# pcb.net
KiCad netlist of a schematic drawn in EAGLE
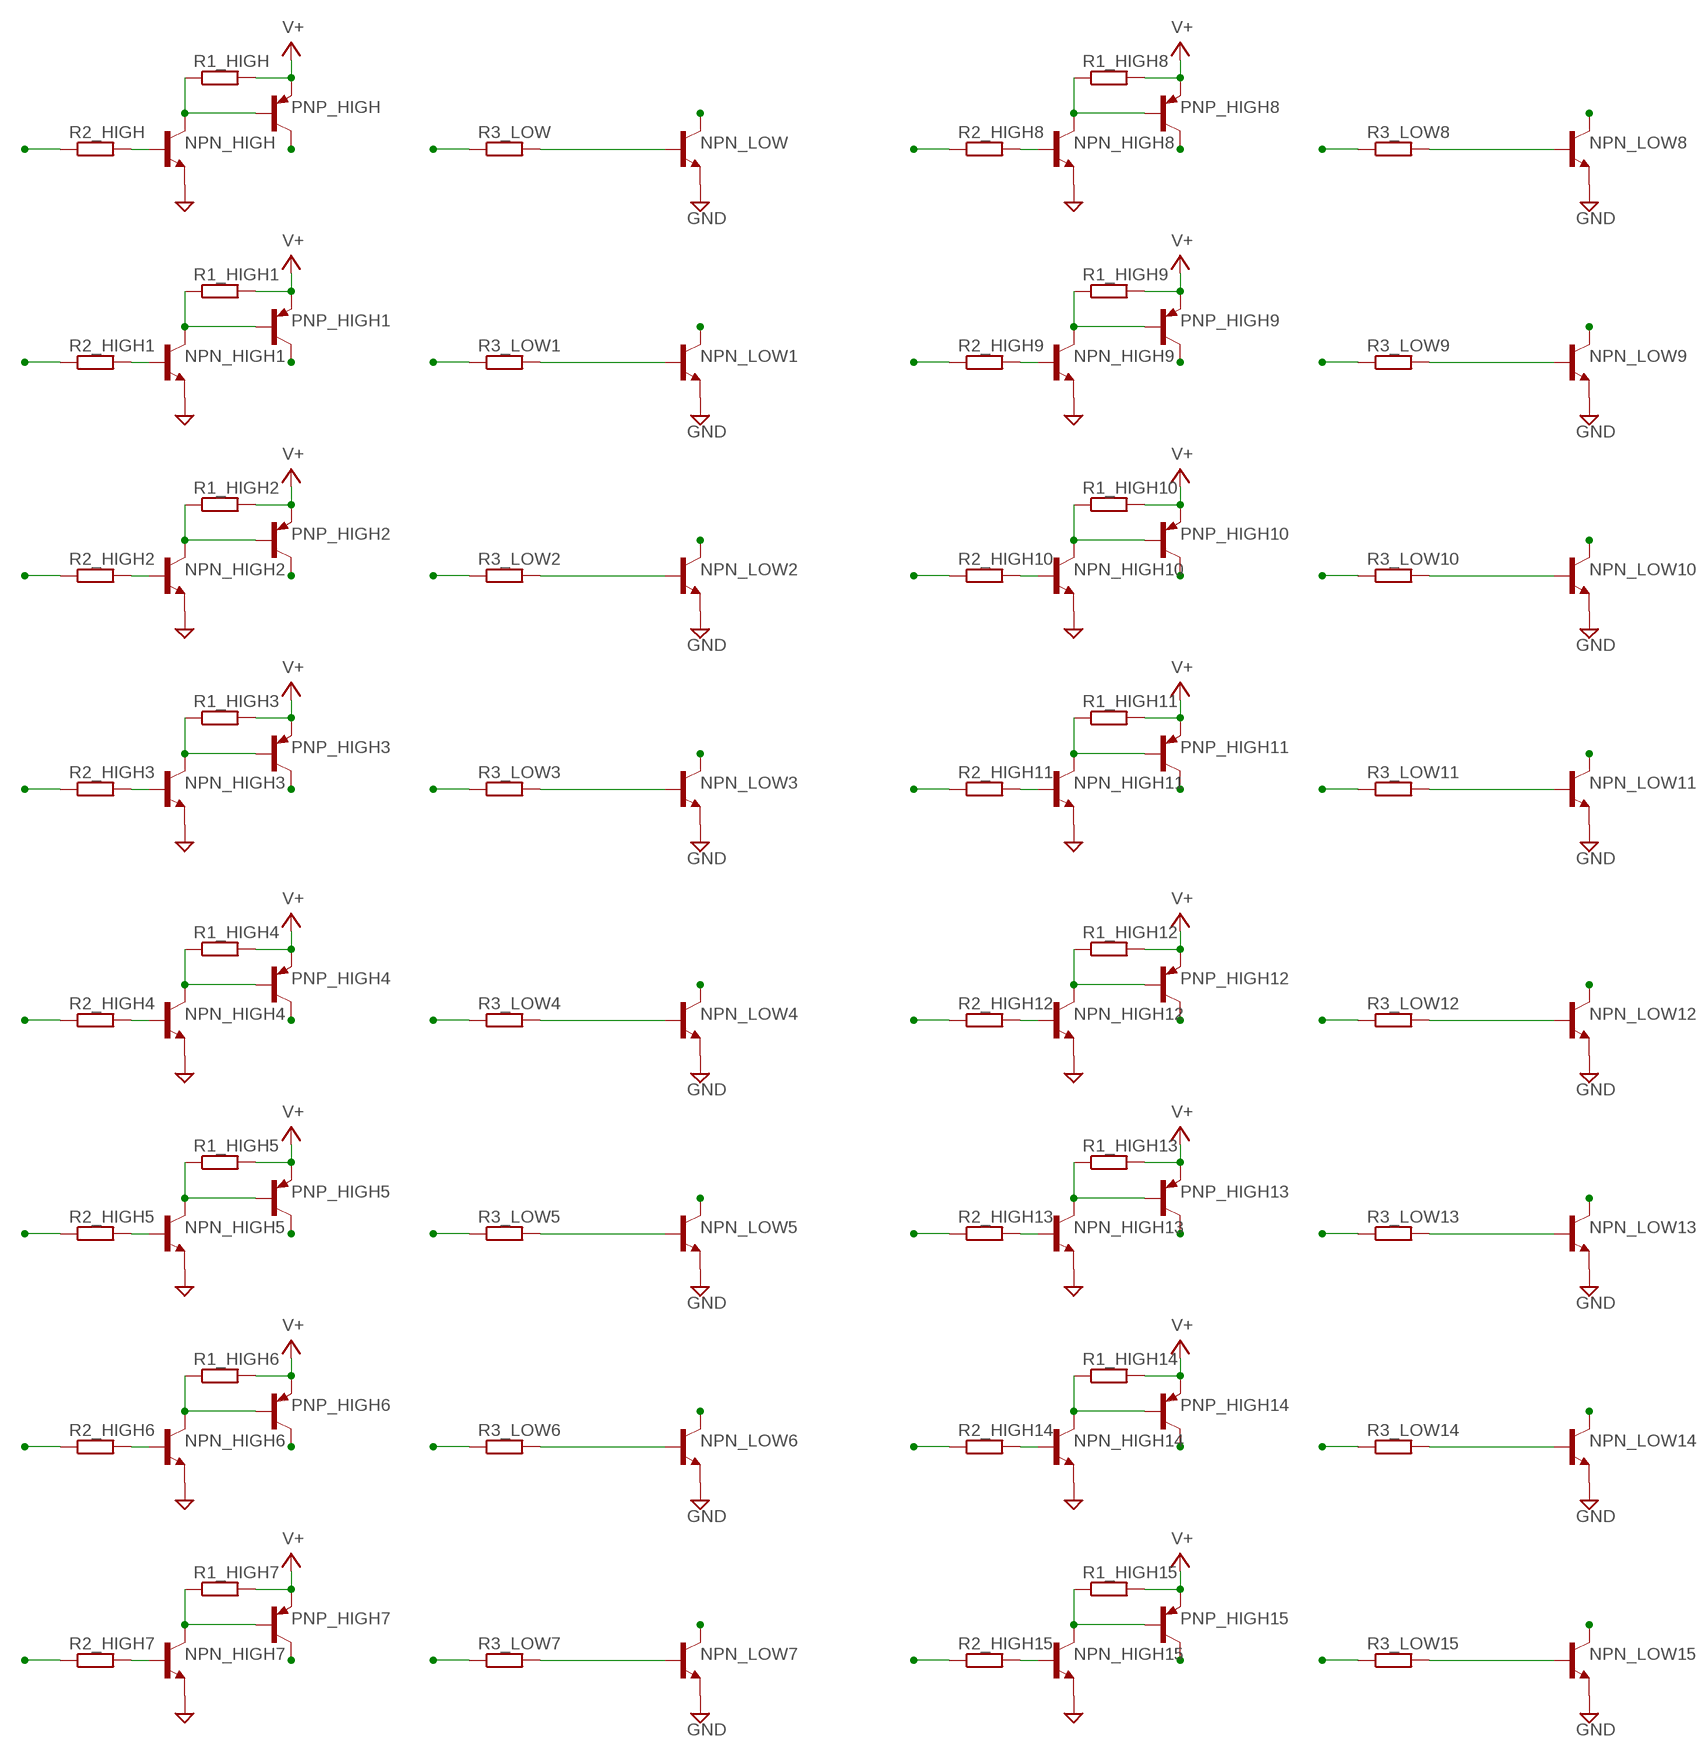
[diagram p0: schematic, sheet 1]

(export (version "E")
  (design (tool "Eeschema 10.0.6"))
  (components
    (comp (ref "NPN_HIGH")
      (value "-NPN-TO92-ECB")
      (footprint "eagle-import:TO92-ECB")
      (libsource (lib "eagle-import") (part "-NPN-TO92-ECB"))
    )
    (comp (ref "NPN_HIGH1")
      (value "-NPN-TO92-ECB")
      (footprint "eagle-import:TO92-ECB")
      (libsource (lib "eagle-import") (part "-NPN-TO92-ECB"))
    )
    (comp (ref "NPN_HIGH2")
      (value "-NPN-TO92-ECB")
      (footprint "eagle-import:TO92-ECB")
      (libsource (lib "eagle-import") (part "-NPN-TO92-ECB"))
    )
    (comp (ref "NPN_HIGH3")
      (value "-NPN-TO92-ECB")
      (footprint "eagle-import:TO92-ECB")
      (libsource (lib "eagle-import") (part "-NPN-TO92-ECB"))
    )
    (comp (ref "NPN_HIGH4")
      (value "-NPN-TO92-ECB")
      (footprint "eagle-import:TO92-ECB")
      (libsource (lib "eagle-import") (part "-NPN-TO92-ECB"))
    )
    (comp (ref "NPN_HIGH5")
      (value "-NPN-TO92-ECB")
      (footprint "eagle-import:TO92-ECB")
      (libsource (lib "eagle-import") (part "-NPN-TO92-ECB"))
    )
    (comp (ref "NPN_HIGH6")
      (value "-NPN-TO92-ECB")
      (footprint "eagle-import:TO92-ECB")
      (libsource (lib "eagle-import") (part "-NPN-TO92-ECB"))
    )
    (comp (ref "NPN_HIGH7")
      (value "-NPN-TO92-ECB")
      (footprint "eagle-import:TO92-ECB")
      (libsource (lib "eagle-import") (part "-NPN-TO92-ECB"))
    )
    (comp (ref "NPN_HIGH8")
      (value "-NPN-TO92-ECB")
      (footprint "eagle-import:TO92-ECB")
      (libsource (lib "eagle-import") (part "-NPN-TO92-ECB"))
    )
    (comp (ref "NPN_HIGH9")
      (value "-NPN-TO92-ECB")
      (footprint "eagle-import:TO92-ECB")
      (libsource (lib "eagle-import") (part "-NPN-TO92-ECB"))
    )
    (comp (ref "NPN_HIGH10")
      (value "-NPN-TO92-ECB")
      (footprint "eagle-import:TO92-ECB")
      (libsource (lib "eagle-import") (part "-NPN-TO92-ECB"))
    )
    (comp (ref "NPN_HIGH11")
      (value "-NPN-TO92-ECB")
      (footprint "eagle-import:TO92-ECB")
      (libsource (lib "eagle-import") (part "-NPN-TO92-ECB"))
    )
    (comp (ref "NPN_HIGH12")
      (value "-NPN-TO92-ECB")
      (footprint "eagle-import:TO92-ECB")
      (libsource (lib "eagle-import") (part "-NPN-TO92-ECB"))
    )
    (comp (ref "NPN_HIGH13")
      (value "-NPN-TO92-ECB")
      (footprint "eagle-import:TO92-ECB")
      (libsource (lib "eagle-import") (part "-NPN-TO92-ECB"))
    )
    (comp (ref "NPN_HIGH14")
      (value "-NPN-TO92-ECB")
      (footprint "eagle-import:TO92-ECB")
      (libsource (lib "eagle-import") (part "-NPN-TO92-ECB"))
    )
    (comp (ref "NPN_HIGH15")
      (value "-NPN-TO92-ECB")
      (footprint "eagle-import:TO92-ECB")
      (libsource (lib "eagle-import") (part "-NPN-TO92-ECB"))
    )
    (comp (ref "NPN_LOW")
      (value "-NPN-TO92-ECB")
      (footprint "eagle-import:TO92-ECB")
      (libsource (lib "eagle-import") (part "-NPN-TO92-ECB"))
    )
    (comp (ref "NPN_LOW1")
      (value "-NPN-TO92-ECB")
      (footprint "eagle-import:TO92-ECB")
      (libsource (lib "eagle-import") (part "-NPN-TO92-ECB"))
    )
    (comp (ref "NPN_LOW2")
      (value "-NPN-TO92-ECB")
      (footprint "eagle-import:TO92-ECB")
      (libsource (lib "eagle-import") (part "-NPN-TO92-ECB"))
    )
    (comp (ref "NPN_LOW3")
      (value "-NPN-TO92-ECB")
      (footprint "eagle-import:TO92-ECB")
      (libsource (lib "eagle-import") (part "-NPN-TO92-ECB"))
    )
    (comp (ref "NPN_LOW4")
      (value "-NPN-TO92-ECB")
      (footprint "eagle-import:TO92-ECB")
      (libsource (lib "eagle-import") (part "-NPN-TO92-ECB"))
    )
    (comp (ref "NPN_LOW5")
      (value "-NPN-TO92-ECB")
      (footprint "eagle-import:TO92-ECB")
      (libsource (lib "eagle-import") (part "-NPN-TO92-ECB"))
    )
    (comp (ref "NPN_LOW6")
      (value "-NPN-TO92-ECB")
      (footprint "eagle-import:TO92-ECB")
      (libsource (lib "eagle-import") (part "-NPN-TO92-ECB"))
    )
    (comp (ref "NPN_LOW7")
      (value "-NPN-TO92-ECB")
      (footprint "eagle-import:TO92-ECB")
      (libsource (lib "eagle-import") (part "-NPN-TO92-ECB"))
    )
    (comp (ref "NPN_LOW8")
      (value "-NPN-TO92-ECB")
      (footprint "eagle-import:TO92-ECB")
      (libsource (lib "eagle-import") (part "-NPN-TO92-ECB"))
    )
    (comp (ref "NPN_LOW9")
      (value "-NPN-TO92-ECB")
      (footprint "eagle-import:TO92-ECB")
      (libsource (lib "eagle-import") (part "-NPN-TO92-ECB"))
    )
    (comp (ref "NPN_LOW10")
      (value "-NPN-TO92-ECB")
      (footprint "eagle-import:TO92-ECB")
      (libsource (lib "eagle-import") (part "-NPN-TO92-ECB"))
    )
    (comp (ref "NPN_LOW11")
      (value "-NPN-TO92-ECB")
      (footprint "eagle-import:TO92-ECB")
      (libsource (lib "eagle-import") (part "-NPN-TO92-ECB"))
    )
    (comp (ref "NPN_LOW12")
      (value "-NPN-TO92-ECB")
      (footprint "eagle-import:TO92-ECB")
      (libsource (lib "eagle-import") (part "-NPN-TO92-ECB"))
    )
    (comp (ref "NPN_LOW13")
      (value "-NPN-TO92-ECB")
      (footprint "eagle-import:TO92-ECB")
      (libsource (lib "eagle-import") (part "-NPN-TO92-ECB"))
    )
    (comp (ref "NPN_LOW14")
      (value "-NPN-TO92-ECB")
      (footprint "eagle-import:TO92-ECB")
      (libsource (lib "eagle-import") (part "-NPN-TO92-ECB"))
    )
    (comp (ref "NPN_LOW15")
      (value "-NPN-TO92-ECB")
      (footprint "eagle-import:TO92-ECB")
      (libsource (lib "eagle-import") (part "-NPN-TO92-ECB"))
    )
    (comp (ref "PNP_HIGH")
      (value "-PNP-TO92-BEC")
      (footprint "eagle-import:TO92-BEC")
      (libsource (lib "eagle-import") (part "-PNP-TO92-BEC"))
    )
    (comp (ref "PNP_HIGH1")
      (value "-PNP-TO92-BEC")
      (footprint "eagle-import:TO92-BEC")
      (libsource (lib "eagle-import") (part "-PNP-TO92-BEC"))
    )
    (comp (ref "PNP_HIGH2")
      (value "-PNP-TO92-BEC")
      (footprint "eagle-import:TO92-BEC")
      (libsource (lib "eagle-import") (part "-PNP-TO92-BEC"))
    )
    (comp (ref "PNP_HIGH3")
      (value "-PNP-TO92-BEC")
      (footprint "eagle-import:TO92-BEC")
      (libsource (lib "eagle-import") (part "-PNP-TO92-BEC"))
    )
    (comp (ref "PNP_HIGH4")
      (value "-PNP-TO92-BEC")
      (footprint "eagle-import:TO92-BEC")
      (libsource (lib "eagle-import") (part "-PNP-TO92-BEC"))
    )
    (comp (ref "PNP_HIGH5")
      (value "-PNP-TO92-BEC")
      (footprint "eagle-import:TO92-BEC")
      (libsource (lib "eagle-import") (part "-PNP-TO92-BEC"))
    )
    (comp (ref "PNP_HIGH6")
      (value "-PNP-TO92-BEC")
      (footprint "eagle-import:TO92-BEC")
      (libsource (lib "eagle-import") (part "-PNP-TO92-BEC"))
    )
    (comp (ref "PNP_HIGH7")
      (value "-PNP-TO92-BEC")
      (footprint "eagle-import:TO92-BEC")
      (libsource (lib "eagle-import") (part "-PNP-TO92-BEC"))
    )
    (comp (ref "PNP_HIGH8")
      (value "-PNP-TO92-BEC")
      (footprint "eagle-import:TO92-BEC")
      (libsource (lib "eagle-import") (part "-PNP-TO92-BEC"))
    )
    (comp (ref "PNP_HIGH9")
      (value "-PNP-TO92-BEC")
      (footprint "eagle-import:TO92-BEC")
      (libsource (lib "eagle-import") (part "-PNP-TO92-BEC"))
    )
    (comp (ref "PNP_HIGH10")
      (value "-PNP-TO92-BEC")
      (footprint "eagle-import:TO92-BEC")
      (libsource (lib "eagle-import") (part "-PNP-TO92-BEC"))
    )
    (comp (ref "PNP_HIGH11")
      (value "-PNP-TO92-BEC")
      (footprint "eagle-import:TO92-BEC")
      (libsource (lib "eagle-import") (part "-PNP-TO92-BEC"))
    )
    (comp (ref "PNP_HIGH12")
      (value "-PNP-TO92-BEC")
      (footprint "eagle-import:TO92-BEC")
      (libsource (lib "eagle-import") (part "-PNP-TO92-BEC"))
    )
    (comp (ref "PNP_HIGH13")
      (value "-PNP-TO92-BEC")
      (footprint "eagle-import:TO92-BEC")
      (libsource (lib "eagle-import") (part "-PNP-TO92-BEC"))
    )
    (comp (ref "PNP_HIGH14")
      (value "-PNP-TO92-BEC")
      (footprint "eagle-import:TO92-BEC")
      (libsource (lib "eagle-import") (part "-PNP-TO92-BEC"))
    )
    (comp (ref "PNP_HIGH15")
      (value "-PNP-TO92-BEC")
      (footprint "eagle-import:TO92-BEC")
      (libsource (lib "eagle-import") (part "-PNP-TO92-BEC"))
    )
    (comp (ref "R1_HIGH")
      (value "R-EU_0613/15")
      (footprint "eagle-import:P0613_15")
      (libsource (lib "eagle-import") (part "R-EU_0613/15"))
    )
    (comp (ref "R1_HIGH1")
      (value "R-EU_0613/15")
      (footprint "eagle-import:P0613_15")
      (libsource (lib "eagle-import") (part "R-EU_0613/15"))
    )
    (comp (ref "R1_HIGH2")
      (value "R-EU_0613/15")
      (footprint "eagle-import:P0613_15")
      (libsource (lib "eagle-import") (part "R-EU_0613/15"))
    )
    (comp (ref "R1_HIGH3")
      (value "R-EU_0613/15")
      (footprint "eagle-import:P0613_15")
      (libsource (lib "eagle-import") (part "R-EU_0613/15"))
    )
    (comp (ref "R1_HIGH4")
      (value "R-EU_0613/15")
      (footprint "eagle-import:P0613_15")
      (libsource (lib "eagle-import") (part "R-EU_0613/15"))
    )
    (comp (ref "R1_HIGH5")
      (value "R-EU_0613/15")
      (footprint "eagle-import:P0613_15")
      (libsource (lib "eagle-import") (part "R-EU_0613/15"))
    )
    (comp (ref "R1_HIGH6")
      (value "R-EU_0613/15")
      (footprint "eagle-import:P0613_15")
      (libsource (lib "eagle-import") (part "R-EU_0613/15"))
    )
    (comp (ref "R1_HIGH7")
      (value "R-EU_0613/15")
      (footprint "eagle-import:P0613_15")
      (libsource (lib "eagle-import") (part "R-EU_0613/15"))
    )
    (comp (ref "R1_HIGH8")
      (value "R-EU_0613/15")
      (footprint "eagle-import:P0613_15")
      (libsource (lib "eagle-import") (part "R-EU_0613/15"))
    )
    (comp (ref "R1_HIGH9")
      (value "R-EU_0613/15")
      (footprint "eagle-import:P0613_15")
      (libsource (lib "eagle-import") (part "R-EU_0613/15"))
    )
    (comp (ref "R1_HIGH10")
      (value "R-EU_0613/15")
      (footprint "eagle-import:P0613_15")
      (libsource (lib "eagle-import") (part "R-EU_0613/15"))
    )
    (comp (ref "R1_HIGH11")
      (value "R-EU_0613/15")
      (footprint "eagle-import:P0613_15")
      (libsource (lib "eagle-import") (part "R-EU_0613/15"))
    )
    (comp (ref "R1_HIGH12")
      (value "R-EU_0613/15")
      (footprint "eagle-import:P0613_15")
      (libsource (lib "eagle-import") (part "R-EU_0613/15"))
    )
    (comp (ref "R1_HIGH13")
      (value "R-EU_0613/15")
      (footprint "eagle-import:P0613_15")
      (libsource (lib "eagle-import") (part "R-EU_0613/15"))
    )
    (comp (ref "R1_HIGH14")
      (value "R-EU_0613/15")
      (footprint "eagle-import:P0613_15")
      (libsource (lib "eagle-import") (part "R-EU_0613/15"))
    )
    (comp (ref "R1_HIGH15")
      (value "R-EU_0613/15")
      (footprint "eagle-import:P0613_15")
      (libsource (lib "eagle-import") (part "R-EU_0613/15"))
    )
    (comp (ref "R2_HIGH")
      (value "R-EU_0613/15")
      (footprint "eagle-import:P0613_15")
      (libsource (lib "eagle-import") (part "R-EU_0613/15"))
    )
    (comp (ref "R2_HIGH1")
      (value "R-EU_0613/15")
      (footprint "eagle-import:P0613_15")
      (libsource (lib "eagle-import") (part "R-EU_0613/15"))
    )
    (comp (ref "R2_HIGH2")
      (value "R-EU_0613/15")
      (footprint "eagle-import:P0613_15")
      (libsource (lib "eagle-import") (part "R-EU_0613/15"))
    )
    (comp (ref "R2_HIGH3")
      (value "R-EU_0613/15")
      (footprint "eagle-import:P0613_15")
      (libsource (lib "eagle-import") (part "R-EU_0613/15"))
    )
    (comp (ref "R2_HIGH4")
      (value "R-EU_0613/15")
      (footprint "eagle-import:P0613_15")
      (libsource (lib "eagle-import") (part "R-EU_0613/15"))
    )
    (comp (ref "R2_HIGH5")
      (value "R-EU_0613/15")
      (footprint "eagle-import:P0613_15")
      (libsource (lib "eagle-import") (part "R-EU_0613/15"))
    )
    (comp (ref "R2_HIGH6")
      (value "R-EU_0613/15")
      (footprint "eagle-import:P0613_15")
      (libsource (lib "eagle-import") (part "R-EU_0613/15"))
    )
    (comp (ref "R2_HIGH7")
      (value "R-EU_0613/15")
      (footprint "eagle-import:P0613_15")
      (libsource (lib "eagle-import") (part "R-EU_0613/15"))
    )
    (comp (ref "R2_HIGH8")
      (value "R-EU_0613/15")
      (footprint "eagle-import:P0613_15")
      (libsource (lib "eagle-import") (part "R-EU_0613/15"))
    )
    (comp (ref "R2_HIGH9")
      (value "R-EU_0613/15")
      (footprint "eagle-import:P0613_15")
      (libsource (lib "eagle-import") (part "R-EU_0613/15"))
    )
    (comp (ref "R2_HIGH10")
      (value "R-EU_0613/15")
      (footprint "eagle-import:P0613_15")
      (libsource (lib "eagle-import") (part "R-EU_0613/15"))
    )
    (comp (ref "R2_HIGH11")
      (value "R-EU_0613/15")
      (footprint "eagle-import:P0613_15")
      (libsource (lib "eagle-import") (part "R-EU_0613/15"))
    )
    (comp (ref "R2_HIGH12")
      (value "R-EU_0613/15")
      (footprint "eagle-import:P0613_15")
      (libsource (lib "eagle-import") (part "R-EU_0613/15"))
    )
    (comp (ref "R2_HIGH13")
      (value "R-EU_0613/15")
      (footprint "eagle-import:P0613_15")
      (libsource (lib "eagle-import") (part "R-EU_0613/15"))
    )
    (comp (ref "R2_HIGH14")
      (value "R-EU_0613/15")
      (footprint "eagle-import:P0613_15")
      (libsource (lib "eagle-import") (part "R-EU_0613/15"))
    )
    (comp (ref "R2_HIGH15")
      (value "R-EU_0613/15")
      (footprint "eagle-import:P0613_15")
      (libsource (lib "eagle-import") (part "R-EU_0613/15"))
    )
    (comp (ref "R3_LOW")
      (value "R-EU_0613/15")
      (footprint "eagle-import:P0613_15")
      (libsource (lib "eagle-import") (part "R-EU_0613/15"))
    )
    (comp (ref "R3_LOW1")
      (value "R-EU_0613/15")
      (footprint "eagle-import:P0613_15")
      (libsource (lib "eagle-import") (part "R-EU_0613/15"))
    )
    (comp (ref "R3_LOW2")
      (value "R-EU_0613/15")
      (footprint "eagle-import:P0613_15")
      (libsource (lib "eagle-import") (part "R-EU_0613/15"))
    )
    (comp (ref "R3_LOW3")
      (value "R-EU_0613/15")
      (footprint "eagle-import:P0613_15")
      (libsource (lib "eagle-import") (part "R-EU_0613/15"))
    )
    (comp (ref "R3_LOW4")
      (value "R-EU_0613/15")
      (footprint "eagle-import:P0613_15")
      (libsource (lib "eagle-import") (part "R-EU_0613/15"))
    )
    (comp (ref "R3_LOW5")
      (value "R-EU_0613/15")
      (footprint "eagle-import:P0613_15")
      (libsource (lib "eagle-import") (part "R-EU_0613/15"))
    )
    (comp (ref "R3_LOW6")
      (value "R-EU_0613/15")
      (footprint "eagle-import:P0613_15")
      (libsource (lib "eagle-import") (part "R-EU_0613/15"))
    )
    (comp (ref "R3_LOW7")
      (value "R-EU_0613/15")
      (footprint "eagle-import:P0613_15")
      (libsource (lib "eagle-import") (part "R-EU_0613/15"))
    )
    (comp (ref "R3_LOW8")
      (value "R-EU_0613/15")
      (footprint "eagle-import:P0613_15")
      (libsource (lib "eagle-import") (part "R-EU_0613/15"))
    )
    (comp (ref "R3_LOW9")
      (value "R-EU_0613/15")
      (footprint "eagle-import:P0613_15")
      (libsource (lib "eagle-import") (part "R-EU_0613/15"))
    )
    (comp (ref "R3_LOW10")
      (value "R-EU_0613/15")
      (footprint "eagle-import:P0613_15")
      (libsource (lib "eagle-import") (part "R-EU_0613/15"))
    )
    (comp (ref "R3_LOW11")
      (value "R-EU_0613/15")
      (footprint "eagle-import:P0613_15")
      (libsource (lib "eagle-import") (part "R-EU_0613/15"))
    )
    (comp (ref "R3_LOW12")
      (value "R-EU_0613/15")
      (footprint "eagle-import:P0613_15")
      (libsource (lib "eagle-import") (part "R-EU_0613/15"))
    )
    (comp (ref "R3_LOW13")
      (value "R-EU_0613/15")
      (footprint "eagle-import:P0613_15")
      (libsource (lib "eagle-import") (part "R-EU_0613/15"))
    )
    (comp (ref "R3_LOW14")
      (value "R-EU_0613/15")
      (footprint "eagle-import:P0613_15")
      (libsource (lib "eagle-import") (part "R-EU_0613/15"))
    )
    (comp (ref "R3_LOW15")
      (value "R-EU_0613/15")
      (footprint "eagle-import:P0613_15")
      (libsource (lib "eagle-import") (part "R-EU_0613/15"))
    )
  )
  (nets
    (net (code "1") (name "GND") (class "Default")
      (node (ref "NPN_HIGH") (pin "E") (pinfunction "E_E") (pintype "passive"))
      (node (ref "NPN_HIGH1") (pin "E") (pinfunction "E_E") (pintype "passive"))
      (node (ref "NPN_HIGH10") (pin "E") (pinfunction "E_E") (pintype "passive"))
      (node (ref "NPN_HIGH11") (pin "E") (pinfunction "E_E") (pintype "passive"))
      (node (ref "NPN_HIGH12") (pin "E") (pinfunction "E_E") (pintype "passive"))
      (node (ref "NPN_HIGH13") (pin "E") (pinfunction "E_E") (pintype "passive"))
      (node (ref "NPN_HIGH14") (pin "E") (pinfunction "E_E") (pintype "passive"))
      (node (ref "NPN_HIGH15") (pin "E") (pinfunction "E_E") (pintype "passive"))
      (node (ref "NPN_HIGH2") (pin "E") (pinfunction "E_E") (pintype "passive"))
      (node (ref "NPN_HIGH3") (pin "E") (pinfunction "E_E") (pintype "passive"))
      (node (ref "NPN_HIGH4") (pin "E") (pinfunction "E_E") (pintype "passive"))
      (node (ref "NPN_HIGH5") (pin "E") (pinfunction "E_E") (pintype "passive"))
      (node (ref "NPN_HIGH6") (pin "E") (pinfunction "E_E") (pintype "passive"))
      (node (ref "NPN_HIGH7") (pin "E") (pinfunction "E_E") (pintype "passive"))
      (node (ref "NPN_HIGH8") (pin "E") (pinfunction "E_E") (pintype "passive"))
      (node (ref "NPN_HIGH9") (pin "E") (pinfunction "E_E") (pintype "passive"))
      (node (ref "NPN_LOW") (pin "E") (pinfunction "E_E") (pintype "passive"))
      (node (ref "NPN_LOW1") (pin "E") (pinfunction "E_E") (pintype "passive"))
      (node (ref "NPN_LOW10") (pin "E") (pinfunction "E_E") (pintype "passive"))
      (node (ref "NPN_LOW11") (pin "E") (pinfunction "E_E") (pintype "passive"))
      (node (ref "NPN_LOW12") (pin "E") (pinfunction "E_E") (pintype "passive"))
      (node (ref "NPN_LOW13") (pin "E") (pinfunction "E_E") (pintype "passive"))
      (node (ref "NPN_LOW14") (pin "E") (pinfunction "E_E") (pintype "passive"))
      (node (ref "NPN_LOW15") (pin "E") (pinfunction "E_E") (pintype "passive"))
      (node (ref "NPN_LOW2") (pin "E") (pinfunction "E_E") (pintype "passive"))
      (node (ref "NPN_LOW3") (pin "E") (pinfunction "E_E") (pintype "passive"))
      (node (ref "NPN_LOW4") (pin "E") (pinfunction "E_E") (pintype "passive"))
      (node (ref "NPN_LOW5") (pin "E") (pinfunction "E_E") (pintype "passive"))
      (node (ref "NPN_LOW6") (pin "E") (pinfunction "E_E") (pintype "passive"))
      (node (ref "NPN_LOW7") (pin "E") (pinfunction "E_E") (pintype "passive"))
      (node (ref "NPN_LOW8") (pin "E") (pinfunction "E_E") (pintype "passive"))
      (node (ref "NPN_LOW9") (pin "E") (pinfunction "E_E") (pintype "passive"))
    )
    (net (code "2") (name "Net-(NPN_HIGH-PadB)") (class "Default")
      (node (ref "NPN_HIGH") (pin "B") (pinfunction "B_B") (pintype "passive"))
      (node (ref "R2_HIGH") (pin "2") (pinfunction "2_2") (pintype "passive"))
    )
    (net (code "3") (name "Net-(NPN_HIGH-PadC)") (class "Default")
      (node (ref "NPN_HIGH") (pin "C") (pinfunction "C_C") (pintype "passive"))
      (node (ref "PNP_HIGH") (pin "B") (pinfunction "B_B") (pintype "passive"))
      (node (ref "R1_HIGH") (pin "1") (pinfunction "1_1") (pintype "passive"))
    )
    (net (code "4") (name "Net-(NPN_HIGH1-PadB)") (class "Default")
      (node (ref "NPN_HIGH1") (pin "B") (pinfunction "B_B") (pintype "passive"))
      (node (ref "R2_HIGH1") (pin "2") (pinfunction "2_2") (pintype "passive"))
    )
    (net (code "5") (name "Net-(NPN_HIGH1-PadC)") (class "Default")
      (node (ref "NPN_HIGH1") (pin "C") (pinfunction "C_C") (pintype "passive"))
      (node (ref "PNP_HIGH1") (pin "B") (pinfunction "B_B") (pintype "passive"))
      (node (ref "R1_HIGH1") (pin "1") (pinfunction "1_1") (pintype "passive"))
    )
    (net (code "6") (name "Net-(NPN_HIGH2-PadB)") (class "Default")
      (node (ref "NPN_HIGH2") (pin "B") (pinfunction "B_B") (pintype "passive"))
      (node (ref "R2_HIGH2") (pin "2") (pinfunction "2_2") (pintype "passive"))
    )
    (net (code "7") (name "Net-(NPN_HIGH2-PadC)") (class "Default")
      (node (ref "NPN_HIGH2") (pin "C") (pinfunction "C_C") (pintype "passive"))
      (node (ref "PNP_HIGH2") (pin "B") (pinfunction "B_B") (pintype "passive"))
      (node (ref "R1_HIGH2") (pin "1") (pinfunction "1_1") (pintype "passive"))
    )
    (net (code "8") (name "Net-(NPN_HIGH3-PadB)") (class "Default")
      (node (ref "NPN_HIGH3") (pin "B") (pinfunction "B_B") (pintype "passive"))
      (node (ref "R2_HIGH3") (pin "2") (pinfunction "2_2") (pintype "passive"))
    )
    (net (code "9") (name "Net-(NPN_HIGH3-PadC)") (class "Default")
      (node (ref "NPN_HIGH3") (pin "C") (pinfunction "C_C") (pintype "passive"))
      (node (ref "PNP_HIGH3") (pin "B") (pinfunction "B_B") (pintype "passive"))
      (node (ref "R1_HIGH3") (pin "1") (pinfunction "1_1") (pintype "passive"))
    )
    (net (code "10") (name "Net-(NPN_HIGH4-PadB)") (class "Default")
      (node (ref "NPN_HIGH4") (pin "B") (pinfunction "B_B") (pintype "passive"))
      (node (ref "R2_HIGH4") (pin "2") (pinfunction "2_2") (pintype "passive"))
    )
    (net (code "11") (name "Net-(NPN_HIGH4-PadC)") (class "Default")
      (node (ref "NPN_HIGH4") (pin "C") (pinfunction "C_C") (pintype "passive"))
      (node (ref "PNP_HIGH4") (pin "B") (pinfunction "B_B") (pintype "passive"))
      (node (ref "R1_HIGH4") (pin "1") (pinfunction "1_1") (pintype "passive"))
    )
    (net (code "12") (name "Net-(NPN_HIGH5-PadB)") (class "Default")
      (node (ref "NPN_HIGH5") (pin "B") (pinfunction "B_B") (pintype "passive"))
      (node (ref "R2_HIGH5") (pin "2") (pinfunction "2_2") (pintype "passive"))
    )
    (net (code "13") (name "Net-(NPN_HIGH5-PadC)") (class "Default")
      (node (ref "NPN_HIGH5") (pin "C") (pinfunction "C_C") (pintype "passive"))
      (node (ref "PNP_HIGH5") (pin "B") (pinfunction "B_B") (pintype "passive"))
      (node (ref "R1_HIGH5") (pin "1") (pinfunction "1_1") (pintype "passive"))
    )
    (net (code "14") (name "Net-(NPN_HIGH6-PadB)") (class "Default")
      (node (ref "NPN_HIGH6") (pin "B") (pinfunction "B_B") (pintype "passive"))
      (node (ref "R2_HIGH6") (pin "2") (pinfunction "2_2") (pintype "passive"))
    )
    (net (code "15") (name "Net-(NPN_HIGH6-PadC)") (class "Default")
      (node (ref "NPN_HIGH6") (pin "C") (pinfunction "C_C") (pintype "passive"))
      (node (ref "PNP_HIGH6") (pin "B") (pinfunction "B_B") (pintype "passive"))
      (node (ref "R1_HIGH6") (pin "1") (pinfunction "1_1") (pintype "passive"))
    )
    (net (code "16") (name "Net-(NPN_HIGH7-PadB)") (class "Default")
      (node (ref "NPN_HIGH7") (pin "B") (pinfunction "B_B") (pintype "passive"))
      (node (ref "R2_HIGH7") (pin "2") (pinfunction "2_2") (pintype "passive"))
    )
    (net (code "17") (name "Net-(NPN_HIGH7-PadC)") (class "Default")
      (node (ref "NPN_HIGH7") (pin "C") (pinfunction "C_C") (pintype "passive"))
      (node (ref "PNP_HIGH7") (pin "B") (pinfunction "B_B") (pintype "passive"))
      (node (ref "R1_HIGH7") (pin "1") (pinfunction "1_1") (pintype "passive"))
    )
    (net (code "18") (name "Net-(NPN_HIGH8-PadB)") (class "Default")
      (node (ref "NPN_HIGH8") (pin "B") (pinfunction "B_B") (pintype "passive"))
      (node (ref "R2_HIGH8") (pin "2") (pinfunction "2_2") (pintype "passive"))
    )
    (net (code "19") (name "Net-(NPN_HIGH8-PadC)") (class "Default")
      (node (ref "NPN_HIGH8") (pin "C") (pinfunction "C_C") (pintype "passive"))
      (node (ref "PNP_HIGH8") (pin "B") (pinfunction "B_B") (pintype "passive"))
      (node (ref "R1_HIGH8") (pin "1") (pinfunction "1_1") (pintype "passive"))
    )
    (net (code "20") (name "Net-(NPN_HIGH9-PadB)") (class "Default")
      (node (ref "NPN_HIGH9") (pin "B") (pinfunction "B_B") (pintype "passive"))
      (node (ref "R2_HIGH9") (pin "2") (pinfunction "2_2") (pintype "passive"))
    )
    (net (code "21") (name "Net-(NPN_HIGH9-PadC)") (class "Default")
      (node (ref "NPN_HIGH9") (pin "C") (pinfunction "C_C") (pintype "passive"))
      (node (ref "PNP_HIGH9") (pin "B") (pinfunction "B_B") (pintype "passive"))
      (node (ref "R1_HIGH9") (pin "1") (pinfunction "1_1") (pintype "passive"))
    )
    (net (code "22") (name "Net-(NPN_HIGH10-PadB)") (class "Default")
      (node (ref "NPN_HIGH10") (pin "B") (pinfunction "B_B") (pintype "passive"))
      (node (ref "R2_HIGH10") (pin "2") (pinfunction "2_2") (pintype "passive"))
    )
    (net (code "23") (name "Net-(NPN_HIGH10-PadC)") (class "Default")
      (node (ref "NPN_HIGH10") (pin "C") (pinfunction "C_C") (pintype "passive"))
      (node (ref "PNP_HIGH10") (pin "B") (pinfunction "B_B") (pintype "passive"))
      (node (ref "R1_HIGH10") (pin "1") (pinfunction "1_1") (pintype "passive"))
    )
    (net (code "24") (name "Net-(NPN_HIGH11-PadB)") (class "Default")
      (node (ref "NPN_HIGH11") (pin "B") (pinfunction "B_B") (pintype "passive"))
      (node (ref "R2_HIGH11") (pin "2") (pinfunction "2_2") (pintype "passive"))
    )
    (net (code "25") (name "Net-(NPN_HIGH11-PadC)") (class "Default")
      (node (ref "NPN_HIGH11") (pin "C") (pinfunction "C_C") (pintype "passive"))
      (node (ref "PNP_HIGH11") (pin "B") (pinfunction "B_B") (pintype "passive"))
      (node (ref "R1_HIGH11") (pin "1") (pinfunction "1_1") (pintype "passive"))
    )
    (net (code "26") (name "Net-(NPN_HIGH12-PadB)") (class "Default")
      (node (ref "NPN_HIGH12") (pin "B") (pinfunction "B_B") (pintype "passive"))
      (node (ref "R2_HIGH12") (pin "2") (pinfunction "2_2") (pintype "passive"))
    )
    (net (code "27") (name "Net-(NPN_HIGH12-PadC)") (class "Default")
      (node (ref "NPN_HIGH12") (pin "C") (pinfunction "C_C") (pintype "passive"))
      (node (ref "PNP_HIGH12") (pin "B") (pinfunction "B_B") (pintype "passive"))
      (node (ref "R1_HIGH12") (pin "1") (pinfunction "1_1") (pintype "passive"))
    )
    (net (code "28") (name "Net-(NPN_HIGH13-PadB)") (class "Default")
      (node (ref "NPN_HIGH13") (pin "B") (pinfunction "B_B") (pintype "passive"))
      (node (ref "R2_HIGH13") (pin "2") (pinfunction "2_2") (pintype "passive"))
    )
    (net (code "29") (name "Net-(NPN_HIGH13-PadC)") (class "Default")
      (node (ref "NPN_HIGH13") (pin "C") (pinfunction "C_C") (pintype "passive"))
      (node (ref "PNP_HIGH13") (pin "B") (pinfunction "B_B") (pintype "passive"))
      (node (ref "R1_HIGH13") (pin "1") (pinfunction "1_1") (pintype "passive"))
    )
    (net (code "30") (name "Net-(NPN_HIGH14-PadB)") (class "Default")
      (node (ref "NPN_HIGH14") (pin "B") (pinfunction "B_B") (pintype "passive"))
      (node (ref "R2_HIGH14") (pin "2") (pinfunction "2_2") (pintype "passive"))
    )
    (net (code "31") (name "Net-(NPN_HIGH14-PadC)") (class "Default")
      (node (ref "NPN_HIGH14") (pin "C") (pinfunction "C_C") (pintype "passive"))
      (node (ref "PNP_HIGH14") (pin "B") (pinfunction "B_B") (pintype "passive"))
      (node (ref "R1_HIGH14") (pin "1") (pinfunction "1_1") (pintype "passive"))
    )
    (net (code "32") (name "Net-(NPN_HIGH15-PadB)") (class "Default")
      (node (ref "NPN_HIGH15") (pin "B") (pinfunction "B_B") (pintype "passive"))
      (node (ref "R2_HIGH15") (pin "2") (pinfunction "2_2") (pintype "passive"))
    )
    (net (code "33") (name "Net-(NPN_HIGH15-PadC)") (class "Default")
      (node (ref "NPN_HIGH15") (pin "C") (pinfunction "C_C") (pintype "passive"))
      (node (ref "PNP_HIGH15") (pin "B") (pinfunction "B_B") (pintype "passive"))
      (node (ref "R1_HIGH15") (pin "1") (pinfunction "1_1") (pintype "passive"))
    )
    (net (code "34") (name "Net-(NPN_LOW-PadB)") (class "Default")
      (node (ref "NPN_LOW") (pin "B") (pinfunction "B_B") (pintype "passive"))
      (node (ref "R3_LOW") (pin "2") (pinfunction "2_2") (pintype "passive"))
    )
    (net (code "35") (name "Net-(NPN_LOW1-PadB)") (class "Default")
      (node (ref "NPN_LOW1") (pin "B") (pinfunction "B_B") (pintype "passive"))
      (node (ref "R3_LOW1") (pin "2") (pinfunction "2_2") (pintype "passive"))
    )
    (net (code "36") (name "Net-(NPN_LOW2-PadB)") (class "Default")
      (node (ref "NPN_LOW2") (pin "B") (pinfunction "B_B") (pintype "passive"))
      (node (ref "R3_LOW2") (pin "2") (pinfunction "2_2") (pintype "passive"))
    )
    (net (code "37") (name "Net-(NPN_LOW3-PadB)") (class "Default")
      (node (ref "NPN_LOW3") (pin "B") (pinfunction "B_B") (pintype "passive"))
      (node (ref "R3_LOW3") (pin "2") (pinfunction "2_2") (pintype "passive"))
    )
    (net (code "38") (name "Net-(NPN_LOW4-PadB)") (class "Default")
      (node (ref "NPN_LOW4") (pin "B") (pinfunction "B_B") (pintype "passive"))
      (node (ref "R3_LOW4") (pin "2") (pinfunction "2_2") (pintype "passive"))
    )
    (net (code "39") (name "Net-(NPN_LOW5-PadB)") (class "Default")
      (node (ref "NPN_LOW5") (pin "B") (pinfunction "B_B") (pintype "passive"))
      (node (ref "R3_LOW5") (pin "2") (pinfunction "2_2") (pintype "passive"))
    )
    (net (code "40") (name "Net-(NPN_LOW6-PadB)") (class "Default")
      (node (ref "NPN_LOW6") (pin "B") (pinfunction "B_B") (pintype "passive"))
      (node (ref "R3_LOW6") (pin "2") (pinfunction "2_2") (pintype "passive"))
    )
    (net (code "41") (name "Net-(NPN_LOW7-PadB)") (class "Default")
      (node (ref "NPN_LOW7") (pin "B") (pinfunction "B_B") (pintype "passive"))
      (node (ref "R3_LOW7") (pin "2") (pinfunction "2_2") (pintype "passive"))
    )
    (net (code "42") (name "Net-(NPN_LOW8-PadB)") (class "Default")
      (node (ref "NPN_LOW8") (pin "B") (pinfunction "B_B") (pintype "passive"))
      (node (ref "R3_LOW8") (pin "2") (pinfunction "2_2") (pintype "passive"))
    )
    (net (code "43") (name "Net-(NPN_LOW9-PadB)") (class "Default")
      (node (ref "NPN_LOW9") (pin "B") (pinfunction "B_B") (pintype "passive"))
      (node (ref "R3_LOW9") (pin "2") (pinfunction "2_2") (pintype "passive"))
    )
    (net (code "44") (name "Net-(NPN_LOW10-PadB)") (class "Default")
      (node (ref "NPN_LOW10") (pin "B") (pinfunction "B_B") (pintype "passive"))
      (node (ref "R3_LOW10") (pin "2") (pinfunction "2_2") (pintype "passive"))
    )
    (net (code "45") (name "Net-(NPN_LOW11-PadB)") (class "Default")
      (node (ref "NPN_LOW11") (pin "B") (pinfunction "B_B") (pintype "passive"))
      (node (ref "R3_LOW11") (pin "2") (pinfunction "2_2") (pintype "passive"))
    )
    (net (code "46") (name "Net-(NPN_LOW12-PadB)") (class "Default")
      (node (ref "NPN_LOW12") (pin "B") (pinfunction "B_B") (pintype "passive"))
      (node (ref "R3_LOW12") (pin "2") (pinfunction "2_2") (pintype "passive"))
    )
    (net (code "47") (name "Net-(NPN_LOW13-PadB)") (class "Default")
      (node (ref "NPN_LOW13") (pin "B") (pinfunction "B_B") (pintype "passive"))
      (node (ref "R3_LOW13") (pin "2") (pinfunction "2_2") (pintype "passive"))
    )
    (net (code "48") (name "Net-(NPN_LOW14-PadB)") (class "Default")
      (node (ref "NPN_LOW14") (pin "B") (pinfunction "B_B") (pintype "passive"))
      (node (ref "R3_LOW14") (pin "2") (pinfunction "2_2") (pintype "passive"))
    )
    (net (code "49") (name "Net-(NPN_LOW15-PadB)") (class "Default")
      (node (ref "NPN_LOW15") (pin "B") (pinfunction "B_B") (pintype "passive"))
      (node (ref "R3_LOW15") (pin "2") (pinfunction "2_2") (pintype "passive"))
    )
    (net (code "50") (name "V+") (class "Default")
      (node (ref "PNP_HIGH") (pin "E") (pinfunction "E_E") (pintype "passive"))
      (node (ref "PNP_HIGH1") (pin "E") (pinfunction "E_E") (pintype "passive"))
      (node (ref "PNP_HIGH10") (pin "E") (pinfunction "E_E") (pintype "passive"))
      (node (ref "PNP_HIGH11") (pin "E") (pinfunction "E_E") (pintype "passive"))
      (node (ref "PNP_HIGH12") (pin "E") (pinfunction "E_E") (pintype "passive"))
      (node (ref "PNP_HIGH13") (pin "E") (pinfunction "E_E") (pintype "passive"))
      (node (ref "PNP_HIGH14") (pin "E") (pinfunction "E_E") (pintype "passive"))
      (node (ref "PNP_HIGH15") (pin "E") (pinfunction "E_E") (pintype "passive"))
      (node (ref "PNP_HIGH2") (pin "E") (pinfunction "E_E") (pintype "passive"))
      (node (ref "PNP_HIGH3") (pin "E") (pinfunction "E_E") (pintype "passive"))
      (node (ref "PNP_HIGH4") (pin "E") (pinfunction "E_E") (pintype "passive"))
      (node (ref "PNP_HIGH5") (pin "E") (pinfunction "E_E") (pintype "passive"))
      (node (ref "PNP_HIGH6") (pin "E") (pinfunction "E_E") (pintype "passive"))
      (node (ref "PNP_HIGH7") (pin "E") (pinfunction "E_E") (pintype "passive"))
      (node (ref "PNP_HIGH8") (pin "E") (pinfunction "E_E") (pintype "passive"))
      (node (ref "PNP_HIGH9") (pin "E") (pinfunction "E_E") (pintype "passive"))
      (node (ref "R1_HIGH") (pin "2") (pinfunction "2_2") (pintype "passive"))
      (node (ref "R1_HIGH1") (pin "2") (pinfunction "2_2") (pintype "passive"))
      (node (ref "R1_HIGH10") (pin "2") (pinfunction "2_2") (pintype "passive"))
      (node (ref "R1_HIGH11") (pin "2") (pinfunction "2_2") (pintype "passive"))
      (node (ref "R1_HIGH12") (pin "2") (pinfunction "2_2") (pintype "passive"))
      (node (ref "R1_HIGH13") (pin "2") (pinfunction "2_2") (pintype "passive"))
      (node (ref "R1_HIGH14") (pin "2") (pinfunction "2_2") (pintype "passive"))
      (node (ref "R1_HIGH15") (pin "2") (pinfunction "2_2") (pintype "passive"))
      (node (ref "R1_HIGH2") (pin "2") (pinfunction "2_2") (pintype "passive"))
      (node (ref "R1_HIGH3") (pin "2") (pinfunction "2_2") (pintype "passive"))
      (node (ref "R1_HIGH4") (pin "2") (pinfunction "2_2") (pintype "passive"))
      (node (ref "R1_HIGH5") (pin "2") (pinfunction "2_2") (pintype "passive"))
      (node (ref "R1_HIGH6") (pin "2") (pinfunction "2_2") (pintype "passive"))
      (node (ref "R1_HIGH7") (pin "2") (pinfunction "2_2") (pintype "passive"))
      (node (ref "R1_HIGH8") (pin "2") (pinfunction "2_2") (pintype "passive"))
      (node (ref "R1_HIGH9") (pin "2") (pinfunction "2_2") (pintype "passive"))
    )
    (net (code "51") (name "unconnected-(NPN_LOW-PadC)") (class "Default")
      (node (ref "NPN_LOW") (pin "C") (pinfunction "C_C") (pintype "passive"))
    )
    (net (code "52") (name "unconnected-(NPN_LOW1-PadC)") (class "Default")
      (node (ref "NPN_LOW1") (pin "C") (pinfunction "C_C") (pintype "passive"))
    )
    (net (code "53") (name "unconnected-(NPN_LOW2-PadC)") (class "Default")
      (node (ref "NPN_LOW2") (pin "C") (pinfunction "C_C") (pintype "passive"))
    )
    (net (code "54") (name "unconnected-(NPN_LOW3-PadC)") (class "Default")
      (node (ref "NPN_LOW3") (pin "C") (pinfunction "C_C") (pintype "passive"))
    )
    (net (code "55") (name "unconnected-(NPN_LOW4-PadC)") (class "Default")
      (node (ref "NPN_LOW4") (pin "C") (pinfunction "C_C") (pintype "passive"))
    )
    (net (code "56") (name "unconnected-(NPN_LOW5-PadC)") (class "Default")
      (node (ref "NPN_LOW5") (pin "C") (pinfunction "C_C") (pintype "passive"))
    )
    (net (code "57") (name "unconnected-(NPN_LOW6-PadC)") (class "Default")
      (node (ref "NPN_LOW6") (pin "C") (pinfunction "C_C") (pintype "passive"))
    )
    (net (code "58") (name "unconnected-(NPN_LOW7-PadC)") (class "Default")
      (node (ref "NPN_LOW7") (pin "C") (pinfunction "C_C") (pintype "passive"))
    )
    (net (code "59") (name "unconnected-(NPN_LOW8-PadC)") (class "Default")
      (node (ref "NPN_LOW8") (pin "C") (pinfunction "C_C") (pintype "passive"))
    )
    (net (code "60") (name "unconnected-(NPN_LOW9-PadC)") (class "Default")
      (node (ref "NPN_LOW9") (pin "C") (pinfunction "C_C") (pintype "passive"))
    )
    (net (code "61") (name "unconnected-(NPN_LOW10-PadC)") (class "Default")
      (node (ref "NPN_LOW10") (pin "C") (pinfunction "C_C") (pintype "passive"))
    )
    (net (code "62") (name "unconnected-(NPN_LOW11-PadC)") (class "Default")
      (node (ref "NPN_LOW11") (pin "C") (pinfunction "C_C") (pintype "passive"))
    )
    (net (code "63") (name "unconnected-(NPN_LOW12-PadC)") (class "Default")
      (node (ref "NPN_LOW12") (pin "C") (pinfunction "C_C") (pintype "passive"))
    )
    (net (code "64") (name "unconnected-(NPN_LOW13-PadC)") (class "Default")
      (node (ref "NPN_LOW13") (pin "C") (pinfunction "C_C") (pintype "passive"))
    )
    (net (code "65") (name "unconnected-(NPN_LOW14-PadC)") (class "Default")
      (node (ref "NPN_LOW14") (pin "C") (pinfunction "C_C") (pintype "passive"))
    )
    (net (code "66") (name "unconnected-(NPN_LOW15-PadC)") (class "Default")
      (node (ref "NPN_LOW15") (pin "C") (pinfunction "C_C") (pintype "passive"))
    )
    (net (code "67") (name "unconnected-(PNP_HIGH-PadC)") (class "Default")
      (node (ref "PNP_HIGH") (pin "C") (pinfunction "C_C") (pintype "passive"))
    )
    (net (code "68") (name "unconnected-(PNP_HIGH1-PadC)") (class "Default")
      (node (ref "PNP_HIGH1") (pin "C") (pinfunction "C_C") (pintype "passive"))
    )
    (net (code "69") (name "unconnected-(PNP_HIGH2-PadC)") (class "Default")
      (node (ref "PNP_HIGH2") (pin "C") (pinfunction "C_C") (pintype "passive"))
    )
    (net (code "70") (name "unconnected-(PNP_HIGH3-PadC)") (class "Default")
      (node (ref "PNP_HIGH3") (pin "C") (pinfunction "C_C") (pintype "passive"))
    )
    (net (code "71") (name "unconnected-(PNP_HIGH4-PadC)") (class "Default")
      (node (ref "PNP_HIGH4") (pin "C") (pinfunction "C_C") (pintype "passive"))
    )
    (net (code "72") (name "unconnected-(PNP_HIGH5-PadC)") (class "Default")
      (node (ref "PNP_HIGH5") (pin "C") (pinfunction "C_C") (pintype "passive"))
    )
    (net (code "73") (name "unconnected-(PNP_HIGH6-PadC)") (class "Default")
      (node (ref "PNP_HIGH6") (pin "C") (pinfunction "C_C") (pintype "passive"))
    )
    (net (code "74") (name "unconnected-(PNP_HIGH7-PadC)") (class "Default")
      (node (ref "PNP_HIGH7") (pin "C") (pinfunction "C_C") (pintype "passive"))
    )
    (net (code "75") (name "unconnected-(PNP_HIGH8-PadC)") (class "Default")
      (node (ref "PNP_HIGH8") (pin "C") (pinfunction "C_C") (pintype "passive"))
    )
    (net (code "76") (name "unconnected-(PNP_HIGH9-PadC)") (class "Default")
      (node (ref "PNP_HIGH9") (pin "C") (pinfunction "C_C") (pintype "passive"))
    )
    (net (code "77") (name "unconnected-(PNP_HIGH10-PadC)") (class "Default")
      (node (ref "PNP_HIGH10") (pin "C") (pinfunction "C_C") (pintype "passive"))
    )
    (net (code "78") (name "unconnected-(PNP_HIGH11-PadC)") (class "Default")
      (node (ref "PNP_HIGH11") (pin "C") (pinfunction "C_C") (pintype "passive"))
    )
    (net (code "79") (name "unconnected-(PNP_HIGH12-PadC)") (class "Default")
      (node (ref "PNP_HIGH12") (pin "C") (pinfunction "C_C") (pintype "passive"))
    )
    (net (code "80") (name "unconnected-(PNP_HIGH13-PadC)") (class "Default")
      (node (ref "PNP_HIGH13") (pin "C") (pinfunction "C_C") (pintype "passive"))
    )
    (net (code "81") (name "unconnected-(PNP_HIGH14-PadC)") (class "Default")
      (node (ref "PNP_HIGH14") (pin "C") (pinfunction "C_C") (pintype "passive"))
    )
    (net (code "82") (name "unconnected-(PNP_HIGH15-PadC)") (class "Default")
      (node (ref "PNP_HIGH15") (pin "C") (pinfunction "C_C") (pintype "passive"))
    )
    (net (code "83") (name "unconnected-(R2_HIGH-Pad1)") (class "Default")
      (node (ref "R2_HIGH") (pin "1") (pinfunction "1_1") (pintype "passive"))
    )
    (net (code "84") (name "unconnected-(R2_HIGH1-Pad1)") (class "Default")
      (node (ref "R2_HIGH1") (pin "1") (pinfunction "1_1") (pintype "passive"))
    )
    (net (code "85") (name "unconnected-(R2_HIGH2-Pad1)") (class "Default")
      (node (ref "R2_HIGH2") (pin "1") (pinfunction "1_1") (pintype "passive"))
    )
    (net (code "86") (name "unconnected-(R2_HIGH3-Pad1)") (class "Default")
      (node (ref "R2_HIGH3") (pin "1") (pinfunction "1_1") (pintype "passive"))
    )
    (net (code "87") (name "unconnected-(R2_HIGH4-Pad1)") (class "Default")
      (node (ref "R2_HIGH4") (pin "1") (pinfunction "1_1") (pintype "passive"))
    )
    (net (code "88") (name "unconnected-(R2_HIGH5-Pad1)") (class "Default")
      (node (ref "R2_HIGH5") (pin "1") (pinfunction "1_1") (pintype "passive"))
    )
    (net (code "89") (name "unconnected-(R2_HIGH6-Pad1)") (class "Default")
      (node (ref "R2_HIGH6") (pin "1") (pinfunction "1_1") (pintype "passive"))
    )
    (net (code "90") (name "unconnected-(R2_HIGH7-Pad1)") (class "Default")
      (node (ref "R2_HIGH7") (pin "1") (pinfunction "1_1") (pintype "passive"))
    )
    (net (code "91") (name "unconnected-(R2_HIGH8-Pad1)") (class "Default")
      (node (ref "R2_HIGH8") (pin "1") (pinfunction "1_1") (pintype "passive"))
    )
    (net (code "92") (name "unconnected-(R2_HIGH9-Pad1)") (class "Default")
      (node (ref "R2_HIGH9") (pin "1") (pinfunction "1_1") (pintype "passive"))
    )
    (net (code "93") (name "unconnected-(R2_HIGH10-Pad1)") (class "Default")
      (node (ref "R2_HIGH10") (pin "1") (pinfunction "1_1") (pintype "passive"))
    )
    (net (code "94") (name "unconnected-(R2_HIGH11-Pad1)") (class "Default")
      (node (ref "R2_HIGH11") (pin "1") (pinfunction "1_1") (pintype "passive"))
    )
    (net (code "95") (name "unconnected-(R2_HIGH12-Pad1)") (class "Default")
      (node (ref "R2_HIGH12") (pin "1") (pinfunction "1_1") (pintype "passive"))
    )
    (net (code "96") (name "unconnected-(R2_HIGH13-Pad1)") (class "Default")
      (node (ref "R2_HIGH13") (pin "1") (pinfunction "1_1") (pintype "passive"))
    )
    (net (code "97") (name "unconnected-(R2_HIGH14-Pad1)") (class "Default")
      (node (ref "R2_HIGH14") (pin "1") (pinfunction "1_1") (pintype "passive"))
    )
    (net (code "98") (name "unconnected-(R2_HIGH15-Pad1)") (class "Default")
      (node (ref "R2_HIGH15") (pin "1") (pinfunction "1_1") (pintype "passive"))
    )
    (net (code "99") (name "unconnected-(R3_LOW-Pad1)") (class "Default")
      (node (ref "R3_LOW") (pin "1") (pinfunction "1_1") (pintype "passive"))
    )
    (net (code "100") (name "unconnected-(R3_LOW1-Pad1)") (class "Default")
      (node (ref "R3_LOW1") (pin "1") (pinfunction "1_1") (pintype "passive"))
    )
    (net (code "101") (name "unconnected-(R3_LOW2-Pad1)") (class "Default")
      (node (ref "R3_LOW2") (pin "1") (pinfunction "1_1") (pintype "passive"))
    )
    (net (code "102") (name "unconnected-(R3_LOW3-Pad1)") (class "Default")
      (node (ref "R3_LOW3") (pin "1") (pinfunction "1_1") (pintype "passive"))
    )
    (net (code "103") (name "unconnected-(R3_LOW4-Pad1)") (class "Default")
      (node (ref "R3_LOW4") (pin "1") (pinfunction "1_1") (pintype "passive"))
    )
    (net (code "104") (name "unconnected-(R3_LOW5-Pad1)") (class "Default")
      (node (ref "R3_LOW5") (pin "1") (pinfunction "1_1") (pintype "passive"))
    )
    (net (code "105") (name "unconnected-(R3_LOW6-Pad1)") (class "Default")
      (node (ref "R3_LOW6") (pin "1") (pinfunction "1_1") (pintype "passive"))
    )
    (net (code "106") (name "unconnected-(R3_LOW7-Pad1)") (class "Default")
      (node (ref "R3_LOW7") (pin "1") (pinfunction "1_1") (pintype "passive"))
    )
    (net (code "107") (name "unconnected-(R3_LOW8-Pad1)") (class "Default")
      (node (ref "R3_LOW8") (pin "1") (pinfunction "1_1") (pintype "passive"))
    )
    (net (code "108") (name "unconnected-(R3_LOW9-Pad1)") (class "Default")
      (node (ref "R3_LOW9") (pin "1") (pinfunction "1_1") (pintype "passive"))
    )
    (net (code "109") (name "unconnected-(R3_LOW10-Pad1)") (class "Default")
      (node (ref "R3_LOW10") (pin "1") (pinfunction "1_1") (pintype "passive"))
    )
    (net (code "110") (name "unconnected-(R3_LOW11-Pad1)") (class "Default")
      (node (ref "R3_LOW11") (pin "1") (pinfunction "1_1") (pintype "passive"))
    )
    (net (code "111") (name "unconnected-(R3_LOW12-Pad1)") (class "Default")
      (node (ref "R3_LOW12") (pin "1") (pinfunction "1_1") (pintype "passive"))
    )
    (net (code "112") (name "unconnected-(R3_LOW13-Pad1)") (class "Default")
      (node (ref "R3_LOW13") (pin "1") (pinfunction "1_1") (pintype "passive"))
    )
    (net (code "113") (name "unconnected-(R3_LOW14-Pad1)") (class "Default")
      (node (ref "R3_LOW14") (pin "1") (pinfunction "1_1") (pintype "passive"))
    )
    (net (code "114") (name "unconnected-(R3_LOW15-Pad1)") (class "Default")
      (node (ref "R3_LOW15") (pin "1") (pinfunction "1_1") (pintype "passive"))
    )
  )
)
